# ukl-eagle.net
KiCad netlist of a schematic drawn in EAGLE
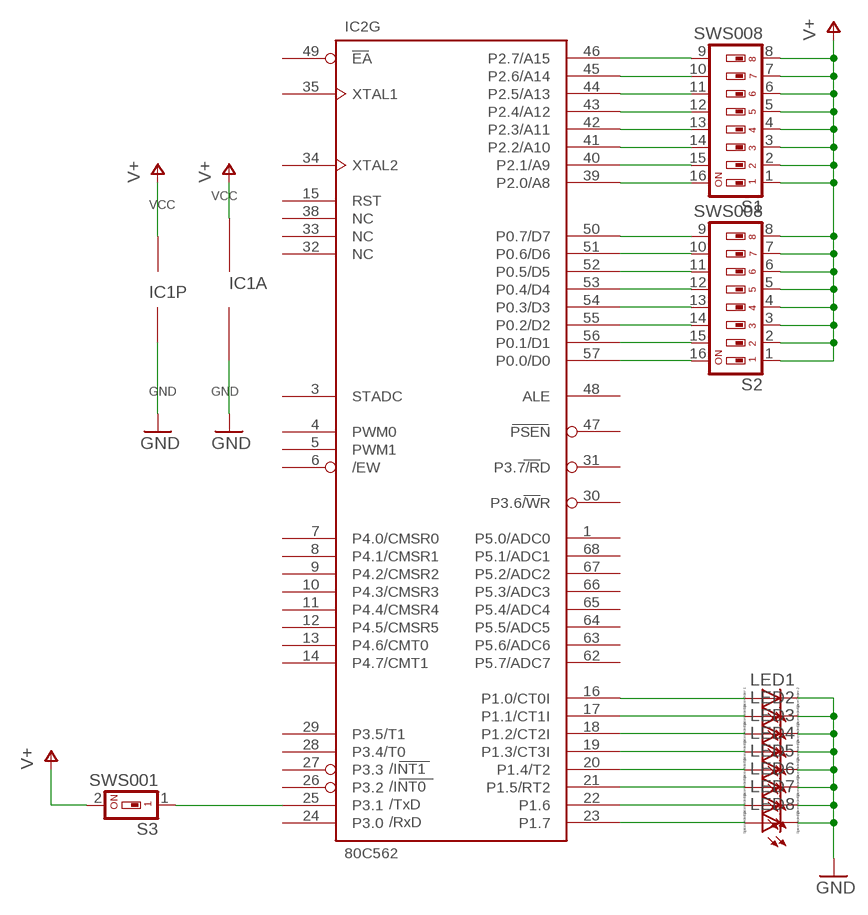
[diagram p0: schematic, sheet 1]

(export (version "E")
  (design (tool "Eeschema 10.0.6"))
  (components
    (comp (ref "IC1")
      (value "80C576SMD")
      (footprint "eagle-import:PLCC44")
      (libsource (lib "eagle-import") (part "80C576SMD"))
    )
    (comp (ref "IC2")
      (value "80C562")
      (footprint "eagle-import:PLCC-S68")
      (fields (field (name "MPN") "P80C562EBA/02,512"))
      (libsource (lib "eagle-import") (part "80C562"))
    )
    (comp (ref "LED1")
      (value "LED_E")
      (footprint "eagle-import:LED_1206")
      (libsource (lib "eagle-import") (part "LED_E"))
    )
    (comp (ref "LED2")
      (value "LED_E")
      (footprint "eagle-import:LED_1206")
      (libsource (lib "eagle-import") (part "LED_E"))
    )
    (comp (ref "LED3")
      (value "LED_E")
      (footprint "eagle-import:LED_1206")
      (libsource (lib "eagle-import") (part "LED_E"))
    )
    (comp (ref "LED4")
      (value "LED_E")
      (footprint "eagle-import:LED_1206")
      (libsource (lib "eagle-import") (part "LED_E"))
    )
    (comp (ref "LED5")
      (value "LED_E")
      (footprint "eagle-import:LED_1206")
      (libsource (lib "eagle-import") (part "LED_E"))
    )
    (comp (ref "LED6")
      (value "LED_E")
      (footprint "eagle-import:LED_1206")
      (libsource (lib "eagle-import") (part "LED_E"))
    )
    (comp (ref "LED7")
      (value "LED_E")
      (footprint "eagle-import:LED_1206")
      (libsource (lib "eagle-import") (part "LED_E"))
    )
    (comp (ref "LED8")
      (value "LED_E")
      (footprint "eagle-import:LED_1206")
      (libsource (lib "eagle-import") (part "LED_E"))
    )
    (comp (ref "S1")
      (value "SWS008")
      (footprint "eagle-import:SMS-008")
      (libsource (lib "eagle-import") (part "SWS008"))
    )
    (comp (ref "S2")
      (value "SWS008")
      (footprint "eagle-import:SMS-008")
      (libsource (lib "eagle-import") (part "SWS008"))
    )
    (comp (ref "S3")
      (value "SWS001")
      (footprint "eagle-import:SMS-001")
      (libsource (lib "eagle-import") (part "SWS001"))
    )
  )
  (nets
    (net (code "1") (name "GND") (class "Default")
      (node (ref "IC1") (pin "22") (pinfunction "GND_22") (pintype "power_in"))
      (node (ref "IC1") (pin "3") (pinfunction "AGND_3") (pintype "power_in"))
      (node (ref "LED1") (pin "C") (pinfunction "C_C") (pintype "passive"))
      (node (ref "LED2") (pin "C") (pinfunction "C_C") (pintype "passive"))
      (node (ref "LED3") (pin "C") (pinfunction "C_C") (pintype "passive"))
      (node (ref "LED4") (pin "C") (pinfunction "C_C") (pintype "passive"))
      (node (ref "LED5") (pin "C") (pinfunction "C_C") (pintype "passive"))
      (node (ref "LED6") (pin "C") (pinfunction "C_C") (pintype "passive"))
      (node (ref "LED7") (pin "C") (pinfunction "C_C") (pintype "passive"))
      (node (ref "LED8") (pin "C") (pinfunction "C_C") (pintype "passive"))
    )
    (net (code "2") (name "Net-(IC2A-P0.0{slash}D0)") (class "Default")
      (node (ref "IC2") (pin "57") (pinfunction "P0.0/D0_57") (pintype "bidirectional"))
      (node (ref "S2") (pin "16") (pinfunction "16_16") (pintype "passive"))
    )
    (net (code "3") (name "Net-(IC2A-P0.1{slash}D1)") (class "Default")
      (node (ref "IC2") (pin "56") (pinfunction "P0.1/D1_56") (pintype "bidirectional"))
      (node (ref "S2") (pin "15") (pinfunction "15_15") (pintype "passive"))
    )
    (net (code "4") (name "Net-(IC2A-P0.2{slash}D2)") (class "Default")
      (node (ref "IC2") (pin "55") (pinfunction "P0.2/D2_55") (pintype "bidirectional"))
      (node (ref "S2") (pin "14") (pinfunction "14_14") (pintype "passive"))
    )
    (net (code "5") (name "Net-(IC2A-P0.3{slash}D3)") (class "Default")
      (node (ref "IC2") (pin "54") (pinfunction "P0.3/D3_54") (pintype "bidirectional"))
      (node (ref "S2") (pin "13") (pinfunction "13_13") (pintype "passive"))
    )
    (net (code "6") (name "Net-(IC2A-P0.4{slash}D4)") (class "Default")
      (node (ref "IC2") (pin "53") (pinfunction "P0.4/D4_53") (pintype "bidirectional"))
      (node (ref "S2") (pin "12") (pinfunction "12_12") (pintype "passive"))
    )
    (net (code "7") (name "Net-(IC2A-P0.5{slash}D5)") (class "Default")
      (node (ref "IC2") (pin "52") (pinfunction "P0.5/D5_52") (pintype "bidirectional"))
      (node (ref "S2") (pin "11") (pinfunction "11_11") (pintype "passive"))
    )
    (net (code "8") (name "Net-(IC2A-P0.6{slash}D6)") (class "Default")
      (node (ref "IC2") (pin "51") (pinfunction "P0.6/D6_51") (pintype "bidirectional"))
      (node (ref "S2") (pin "10") (pinfunction "10_10") (pintype "passive"))
    )
    (net (code "9") (name "Net-(IC2A-P0.7{slash}D7)") (class "Default")
      (node (ref "IC2") (pin "50") (pinfunction "P0.7/D7_50") (pintype "bidirectional"))
      (node (ref "S2") (pin "9") (pinfunction "9_9") (pintype "passive"))
    )
    (net (code "10") (name "Net-(IC2A-P1.0{slash}CT0I)") (class "Default")
      (node (ref "IC2") (pin "16") (pinfunction "P1.0/CT0I_16") (pintype "bidirectional"))
      (node (ref "LED1") (pin "A") (pinfunction "A_A") (pintype "passive"))
    )
    (net (code "11") (name "Net-(IC2A-P1.1{slash}CT1I)") (class "Default")
      (node (ref "IC2") (pin "17") (pinfunction "P1.1/CT1I_17") (pintype "bidirectional"))
      (node (ref "LED2") (pin "A") (pinfunction "A_A") (pintype "passive"))
    )
    (net (code "12") (name "Net-(IC2A-P1.2{slash}CT2I)") (class "Default")
      (node (ref "IC2") (pin "18") (pinfunction "P1.2/CT2I_18") (pintype "bidirectional"))
      (node (ref "LED3") (pin "A") (pinfunction "A_A") (pintype "passive"))
    )
    (net (code "13") (name "Net-(IC2A-P1.3{slash}CT3I)") (class "Default")
      (node (ref "IC2") (pin "19") (pinfunction "P1.3/CT3I_19") (pintype "bidirectional"))
      (node (ref "LED4") (pin "A") (pinfunction "A_A") (pintype "passive"))
    )
    (net (code "14") (name "Net-(IC2A-P1.4{slash}T2)") (class "Default")
      (node (ref "IC2") (pin "20") (pinfunction "P1.4/T2_20") (pintype "bidirectional"))
      (node (ref "LED5") (pin "A") (pinfunction "A_A") (pintype "passive"))
    )
    (net (code "15") (name "Net-(IC2A-P1.5{slash}RT2)") (class "Default")
      (node (ref "IC2") (pin "21") (pinfunction "P1.5/RT2_21") (pintype "bidirectional"))
      (node (ref "LED6") (pin "A") (pinfunction "A_A") (pintype "passive"))
    )
    (net (code "16") (name "Net-(IC2A-P1.6)") (class "Default")
      (node (ref "IC2") (pin "22") (pinfunction "P1.6_22") (pintype "bidirectional"))
      (node (ref "LED7") (pin "A") (pinfunction "A_A") (pintype "passive"))
    )
    (net (code "17") (name "Net-(IC2A-P1.7)") (class "Default")
      (node (ref "IC2") (pin "23") (pinfunction "P1.7_23") (pintype "bidirectional"))
      (node (ref "LED8") (pin "A") (pinfunction "A_A") (pintype "passive"))
    )
    (net (code "18") (name "Net-(IC2A-P2.0{slash}A8)") (class "Default")
      (node (ref "IC2") (pin "39") (pinfunction "P2.0/A8_39") (pintype "output"))
      (node (ref "S1") (pin "16") (pinfunction "16_16") (pintype "passive"))
    )
    (net (code "19") (name "Net-(IC2A-P2.1{slash}A9)") (class "Default")
      (node (ref "IC2") (pin "40") (pinfunction "P2.1/A9_40") (pintype "output"))
      (node (ref "S1") (pin "15") (pinfunction "15_15") (pintype "passive"))
    )
    (net (code "20") (name "Net-(IC2A-P2.2{slash}A10)") (class "Default")
      (node (ref "IC2") (pin "41") (pinfunction "P2.2/A10_41") (pintype "output"))
      (node (ref "S1") (pin "14") (pinfunction "14_14") (pintype "passive"))
    )
    (net (code "21") (name "Net-(IC2A-P2.3{slash}A11)") (class "Default")
      (node (ref "IC2") (pin "42") (pinfunction "P2.3/A11_42") (pintype "output"))
      (node (ref "S1") (pin "13") (pinfunction "13_13") (pintype "passive"))
    )
    (net (code "22") (name "Net-(IC2A-P2.4{slash}A12)") (class "Default")
      (node (ref "IC2") (pin "43") (pinfunction "P2.4/A12_43") (pintype "output"))
      (node (ref "S1") (pin "12") (pinfunction "12_12") (pintype "passive"))
    )
    (net (code "23") (name "Net-(IC2A-P2.5{slash}A13)") (class "Default")
      (node (ref "IC2") (pin "44") (pinfunction "P2.5/A13_44") (pintype "output"))
      (node (ref "S1") (pin "11") (pinfunction "11_11") (pintype "passive"))
    )
    (net (code "24") (name "Net-(IC2A-P2.6{slash}A14)") (class "Default")
      (node (ref "IC2") (pin "45") (pinfunction "P2.6/A14_45") (pintype "output"))
      (node (ref "S1") (pin "10") (pinfunction "10_10") (pintype "passive"))
    )
    (net (code "25") (name "Net-(IC2A-P2.7{slash}A15)") (class "Default")
      (node (ref "IC2") (pin "46") (pinfunction "P2.7/A15_46") (pintype "output"))
      (node (ref "S1") (pin "9") (pinfunction "9_9") (pintype "passive"))
    )
    (net (code "26") (name "Net-(IC2A-P3.1)") (class "Default")
      (node (ref "IC2") (pin "25") (pinfunction "P3.1_25") (pintype "bidirectional"))
      (node (ref "S3") (pin "1") (pinfunction "1_1") (pintype "passive"))
    )
    (net (code "27") (name "V+") (class "Default")
      (node (ref "IC1") (pin "2") (pinfunction "AVCC_2") (pintype "power_in"))
      (node (ref "IC1") (pin "44") (pinfunction "VCC_44") (pintype "power_in"))
      (node (ref "S1") (pin "1") (pinfunction "1_1") (pintype "passive"))
      (node (ref "S1") (pin "2") (pinfunction "2_2") (pintype "passive"))
      (node (ref "S1") (pin "3") (pinfunction "3_3") (pintype "passive"))
      (node (ref "S1") (pin "4") (pinfunction "4_4") (pintype "passive"))
      (node (ref "S1") (pin "5") (pinfunction "5_5") (pintype "passive"))
      (node (ref "S1") (pin "6") (pinfunction "6_6") (pintype "passive"))
      (node (ref "S1") (pin "7") (pinfunction "7_7") (pintype "passive"))
      (node (ref "S1") (pin "8") (pinfunction "8_8") (pintype "passive"))
      (node (ref "S2") (pin "1") (pinfunction "1_1") (pintype "passive"))
      (node (ref "S2") (pin "2") (pinfunction "2_2") (pintype "passive"))
      (node (ref "S2") (pin "3") (pinfunction "3_3") (pintype "passive"))
      (node (ref "S2") (pin "4") (pinfunction "4_4") (pintype "passive"))
      (node (ref "S2") (pin "5") (pinfunction "5_5") (pintype "passive"))
      (node (ref "S2") (pin "6") (pinfunction "6_6") (pintype "passive"))
      (node (ref "S2") (pin "7") (pinfunction "7_7") (pintype "passive"))
      (node (ref "S2") (pin "8") (pinfunction "8_8") (pintype "passive"))
      (node (ref "S3") (pin "2") (pinfunction "2_2") (pintype "passive"))
    )
    (net (code "28") (name "unconnected-(IC2A-ALE-Pad48)") (class "Default")
      (node (ref "IC2") (pin "48") (pinfunction "ALE_48") (pintype "output"))
    )
    (net (code "29") (name "unconnected-(IC2A-EA-Pad49)") (class "Default")
      (node (ref "IC2") (pin "49") (pinfunction "EA_49") (pintype "input"))
    )
    (net (code "30") (name "unconnected-(IC2A-NC-Pad32)") (class "Default")
      (node (ref "IC2") (pin "32") (pinfunction "NC_32") (pintype "no_connect"))
    )
    (net (code "31") (name "unconnected-(IC2A-NC-Pad33)") (class "Default")
      (node (ref "IC2") (pin "33") (pinfunction "NC_33") (pintype "no_connect"))
    )
    (net (code "32") (name "unconnected-(IC2A-NC-Pad38)") (class "Default")
      (node (ref "IC2") (pin "38") (pinfunction "NC_38") (pintype "no_connect"))
    )
    (net (code "33") (name "unconnected-(IC2A-P3.0-Pad24)") (class "Default")
      (node (ref "IC2") (pin "24") (pinfunction "P3.0_24") (pintype "bidirectional"))
    )
    (net (code "34") (name "unconnected-(IC2A-P3.2-Pad26)") (class "Default")
      (node (ref "IC2") (pin "26") (pinfunction "P3.2_26") (pintype "bidirectional"))
    )
    (net (code "35") (name "unconnected-(IC2A-P3.3-Pad27)") (class "Default")
      (node (ref "IC2") (pin "27") (pinfunction "P3.3_27") (pintype "bidirectional"))
    )
    (net (code "36") (name "unconnected-(IC2A-P3.4{slash}T0-Pad28)") (class "Default")
      (node (ref "IC2") (pin "28") (pinfunction "P3.4/T0_28") (pintype "bidirectional"))
    )
    (net (code "37") (name "unconnected-(IC2A-P3.5{slash}T1-Pad29)") (class "Default")
      (node (ref "IC2") (pin "29") (pinfunction "P3.5/T1_29") (pintype "bidirectional"))
    )
    (net (code "38") (name "unconnected-(IC2A-P3.6{slash}WR-Pad30)") (class "Default")
      (node (ref "IC2") (pin "30") (pinfunction "P3.6/WR_30") (pintype "bidirectional"))
    )
    (net (code "39") (name "unconnected-(IC2A-P3.7{slash}RD-Pad31)") (class "Default")
      (node (ref "IC2") (pin "31") (pinfunction "P3.7/RD_31") (pintype "bidirectional"))
    )
    (net (code "40") (name "unconnected-(IC2A-P4.0{slash}CMSR0-Pad7)") (class "Default")
      (node (ref "IC2") (pin "7") (pinfunction "P4.0/CMSR0_7") (pintype "bidirectional"))
    )
    (net (code "41") (name "unconnected-(IC2A-P4.1{slash}CMSR1-Pad8)") (class "Default")
      (node (ref "IC2") (pin "8") (pinfunction "P4.1/CMSR1_8") (pintype "bidirectional"))
    )
    (net (code "42") (name "unconnected-(IC2A-P4.2{slash}CMSR2-Pad9)") (class "Default")
      (node (ref "IC2") (pin "9") (pinfunction "P4.2/CMSR2_9") (pintype "bidirectional"))
    )
    (net (code "43") (name "unconnected-(IC2A-P4.3{slash}CMSR3-Pad10)") (class "Default")
      (node (ref "IC2") (pin "10") (pinfunction "P4.3/CMSR3_10") (pintype "bidirectional"))
    )
    (net (code "44") (name "unconnected-(IC2A-P4.4{slash}CMSR4-Pad11)") (class "Default")
      (node (ref "IC2") (pin "11") (pinfunction "P4.4/CMSR4_11") (pintype "bidirectional"))
    )
    (net (code "45") (name "unconnected-(IC2A-P4.5{slash}CMSR5-Pad12)") (class "Default")
      (node (ref "IC2") (pin "12") (pinfunction "P4.5/CMSR5_12") (pintype "bidirectional"))
    )
    (net (code "46") (name "unconnected-(IC2A-P4.6{slash}CMT0-Pad13)") (class "Default")
      (node (ref "IC2") (pin "13") (pinfunction "P4.6/CMT0_13") (pintype "bidirectional"))
    )
    (net (code "47") (name "unconnected-(IC2A-P4.7{slash}CMT1-Pad14)") (class "Default")
      (node (ref "IC2") (pin "14") (pinfunction "P4.7/CMT1_14") (pintype "bidirectional"))
    )
    (net (code "48") (name "unconnected-(IC2A-P5.0{slash}ADC0-Pad1)") (class "Default")
      (node (ref "IC2") (pin "1") (pinfunction "P5.0/ADC0_1") (pintype "bidirectional"))
    )
    (net (code "49") (name "unconnected-(IC2A-P5.1{slash}ADC1-Pad68)") (class "Default")
      (node (ref "IC2") (pin "68") (pinfunction "P5.1/ADC1_68") (pintype "bidirectional"))
    )
    (net (code "50") (name "unconnected-(IC2A-P5.2{slash}ADC2-Pad67)") (class "Default")
      (node (ref "IC2") (pin "67") (pinfunction "P5.2/ADC2_67") (pintype "bidirectional"))
    )
    (net (code "51") (name "unconnected-(IC2A-P5.3{slash}ADC3-Pad66)") (class "Default")
      (node (ref "IC2") (pin "66") (pinfunction "P5.3/ADC3_66") (pintype "bidirectional"))
    )
    (net (code "52") (name "unconnected-(IC2A-P5.4{slash}ADC4-Pad65)") (class "Default")
      (node (ref "IC2") (pin "65") (pinfunction "P5.4/ADC4_65") (pintype "bidirectional"))
    )
    (net (code "53") (name "unconnected-(IC2A-P5.5{slash}ADC5-Pad64)") (class "Default")
      (node (ref "IC2") (pin "64") (pinfunction "P5.5/ADC5_64") (pintype "bidirectional"))
    )
    (net (code "54") (name "unconnected-(IC2A-P5.6{slash}ADC6-Pad63)") (class "Default")
      (node (ref "IC2") (pin "63") (pinfunction "P5.6/ADC6_63") (pintype "bidirectional"))
    )
    (net (code "55") (name "unconnected-(IC2A-P5.7{slash}ADC7-Pad62)") (class "Default")
      (node (ref "IC2") (pin "62") (pinfunction "P5.7/ADC7_62") (pintype "bidirectional"))
    )
    (net (code "56") (name "unconnected-(IC2A-PSEN-Pad47)") (class "Default")
      (node (ref "IC2") (pin "47") (pinfunction "PSEN_47") (pintype "output"))
    )
    (net (code "57") (name "unconnected-(IC2A-PWM0-Pad4)") (class "Default")
      (node (ref "IC2") (pin "4") (pinfunction "PWM0_4") (pintype "bidirectional"))
    )
    (net (code "58") (name "unconnected-(IC2A-PWM1-Pad5)") (class "Default")
      (node (ref "IC2") (pin "5") (pinfunction "PWM1_5") (pintype "bidirectional"))
    )
    (net (code "59") (name "unconnected-(IC2A-RST-Pad15)") (class "Default")
      (node (ref "IC2") (pin "15") (pinfunction "RST_15") (pintype "input"))
    )
    (net (code "60") (name "unconnected-(IC2A-STADC-Pad3)") (class "Default")
      (node (ref "IC2") (pin "3") (pinfunction "STADC_3") (pintype "bidirectional"))
    )
    (net (code "61") (name "unconnected-(IC2A-XTAL1-Pad35)") (class "Default")
      (node (ref "IC2") (pin "35") (pinfunction "XTAL1_35") (pintype "input"))
    )
    (net (code "62") (name "unconnected-(IC2A-XTAL2-Pad34)") (class "Default")
      (node (ref "IC2") (pin "34") (pinfunction "XTAL2_34") (pintype "input"))
    )
    (net (code "63") (name "unconnected-(IC2A-{slash}EW-Pad6)") (class "Default")
      (node (ref "IC2") (pin "6") (pinfunction "/EW_6") (pintype "bidirectional"))
    )
  )
)
